# Input_Filter.net
KiCad netlist of a schematic drawn in Altium Designer
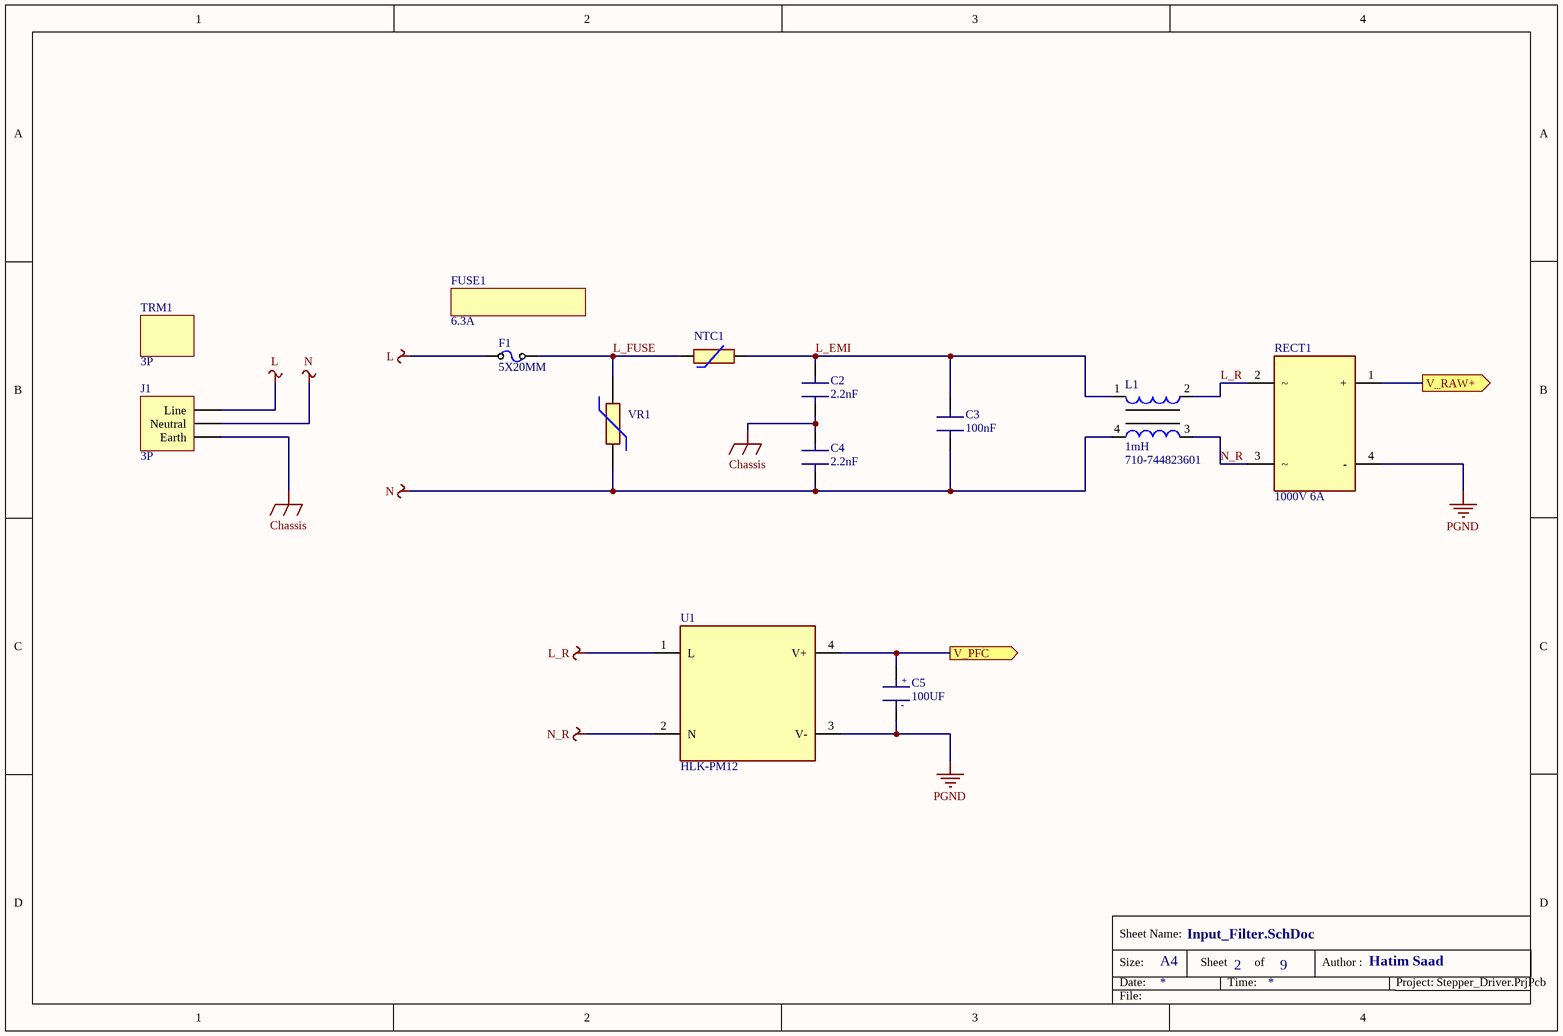
[diagram p0: Input_Filter.SchDoc]

(export (version "E")
  (design (tool "Eeschema 10.0.6"))
  (components
    (comp (ref "C2")
      (value "2.2nF")
      (footprint "CAP: 10MM Ceramic Disc")
      (description "Safety Capacitors 2200pF X760 Y500VAC 20% Y5U")
      (libsource (lib "HZSchLib") (part "VY1222M43Y5UC63V0"))
    )
    (comp (ref "C3")
      (value "100nF")
      (footprint "CAP: 15MM Film Capacitor")
      (description "Safety Capacitors 275vac 0.1uF 20%")
      (libsource (lib "HZSchLib") (part "R46KI310050M1M"))
    )
    (comp (ref "C4")
      (value "2.2nF")
      (footprint "CAP: 10MM Ceramic Disc")
      (description "Safety Capacitors 2200pF X760 Y500VAC 20% Y5U")
      (libsource (lib "HZSchLib") (part "VY1222M43Y5UC63V0"))
    )
    (comp (ref "C5")
      (value "100UF")
      (footprint "CAP SMD 8")
      (description "Aluminium Electrolytic Capacitors - SMD 50V 100uF 20%")
      (libsource (lib "HZSchLib") (part "EDK107M050A9MAA"))
    )
    (comp (ref "F1")
      (value "5X20MM")
      (footprint "FUSE HOLDER 5X20MM")
      (description "Fuse Holder 5X20MM Pitch 22/7 UL94V0 Open")
      (libsource (lib "HZSchLib") (part "0PTF0078P"))
    )
    (comp (ref "FUSE1")
      (value "6.3A")
      (description "Cartridge Fuses FST 5X20 250V 6.3A")
      (libsource (lib "HZSchLib") (part "0034.3125"))
    )
    (comp (ref "J1")
      (value "3P")
      (footprint "691313510003")
      (description "Pluggable Terminal Blocks WR-TBL 300VAC 20A 3P Right Angle")
      (libsource (lib "HZSchLib") (part "691313510003"))
    )
    (comp (ref "L1")
      (value "1mH")
      (footprint "744823601")
      (description "Common Mode Chokes / Filters WE-CMB Choke Type M 1mH 6A 13mOhm")
      (fields (field (name "SUPPLIER PART NUMBER 1") "710-744823601"))
      (libsource (lib "HZSchLib") (part "744823601"))
    )
    (comp (ref "NTC1")
      (value "BN-LG15Y6R0MYB")
      (footprint "NTC Radial: 7.5X1MM")
      (description "NTC (Negative Temperature Coefficient) Thermistors 15 dia Power NTC 6ohm Y kink bulk")
      (libsource (lib "HZSchLib") (part "BN-LG15Y6R0MYB"))
    )
    (comp (ref "RECT1")
      (value "1000V 6A")
      (footprint "TBSG-4")
      (description "Bridge Rectifiers BRIDGE RECTIFIERS 1000V 6A, TBSG")
      (libsource (lib "HZSchLib") (part "TBSA60M-TP"))
    )
    (comp (ref "TRM1")
      (value "3P")
      (description "Pluggable Terminal Blocks WR-TBL 300VAC 20A 3P Right Angle")
      (libsource (lib "HZSchLib") (part "691351500003"))
    )
    (comp (ref "U1")
      (value "HLK-PM12")
      (footprint "HLK-PM01")
      (description "AC-DC Module 3W 220Vac to 12Vdc")
      (libsource (lib "HZSchLib") (part "HLK-PM12"))
    )
    (comp (ref "VR1")
      (value "275VAC")
      (footprint "B72307S0271K101")
      (description "Varistors 7mm, 275Vac, 10%, Compact Series")
      (libsource (lib "HZSchLib") (part "B72307S0271K101"))
    )
  )
  (nets
    (net (code "1") (name "/L_EMI") (class "Default")
      (node (ref "C2") (pin "2") (pinfunction "B_2") (pintype "passive"))
      (node (ref "C3") (pin "2") (pinfunction "B_2") (pintype "passive"))
      (node (ref "L1") (pin "1") (pinfunction "1_1") (pintype "passive"))
      (node (ref "NTC1") (pin "2") (pinfunction "2_2") (pintype "passive"))
    )
    (net (code "2") (name "/L_FUSE") (class "Default")
      (node (ref "F1") (pin "2") (pinfunction "2_2") (pintype "passive"))
      (node (ref "NTC1") (pin "1") (pinfunction "1_1") (pintype "passive"))
      (node (ref "VR1") (pin "2") (pinfunction "2_2") (pintype "passive"))
    )
    (net (code "3") (name "/V_PFC") (class "Default")
      (node (ref "C5") (pin "1") (pinfunction "+_1") (pintype "passive"))
      (node (ref "U1") (pin "4") (pinfunction "V+_4") (pintype "passive"))
    )
    (net (code "4") (name "/V_RAW+") (class "Default")
      (node (ref "RECT1") (pin "1") (pinfunction "+_1") (pintype "passive"))
    )
    (net (code "5") (name "Chassis") (class "Default")
      (node (ref "C2") (pin "1") (pinfunction "A_1") (pintype "passive"))
      (node (ref "C4") (pin "2") (pinfunction "B_2") (pintype "passive"))
      (node (ref "J1") (pin "3") (pinfunction "Earth_3") (pintype "power_in"))
    )
    (net (code "6") (name "L") (class "Default")
      (node (ref "F1") (pin "1") (pinfunction "1_1") (pintype "passive"))
      (node (ref "J1") (pin "1") (pinfunction "Line_1") (pintype "passive"))
    )
    (net (code "7") (name "L_R") (class "Default")
      (node (ref "L1") (pin "2") (pinfunction "2_2") (pintype "passive"))
      (node (ref "RECT1") (pin "2") (pinfunction "~_2") (pintype "passive"))
      (node (ref "U1") (pin "1") (pinfunction "L_1") (pintype "passive"))
    )
    (net (code "8") (name "N") (class "Default")
      (node (ref "C3") (pin "1") (pinfunction "A_1") (pintype "passive"))
      (node (ref "C4") (pin "1") (pinfunction "A_1") (pintype "passive"))
      (node (ref "J1") (pin "2") (pinfunction "Neutral_2") (pintype "passive"))
      (node (ref "L1") (pin "4") (pinfunction "4_4") (pintype "passive"))
      (node (ref "VR1") (pin "1") (pinfunction "1_1") (pintype "passive"))
    )
    (net (code "9") (name "N_R") (class "Default")
      (node (ref "L1") (pin "3") (pinfunction "3_3") (pintype "passive"))
      (node (ref "RECT1") (pin "3") (pinfunction "~_3") (pintype "passive"))
      (node (ref "U1") (pin "2") (pinfunction "N_2") (pintype "passive"))
    )
    (net (code "10") (name "PGND") (class "Default")
      (node (ref "C5") (pin "2") (pinfunction "-_2") (pintype "passive"))
      (node (ref "RECT1") (pin "4") (pinfunction "-_4") (pintype "passive"))
      (node (ref "U1") (pin "3") (pinfunction "V-_3") (pintype "passive"))
    )
  )
)
